# Parking_System.net
KiCad netlist of a schematic drawn in Altium Designer
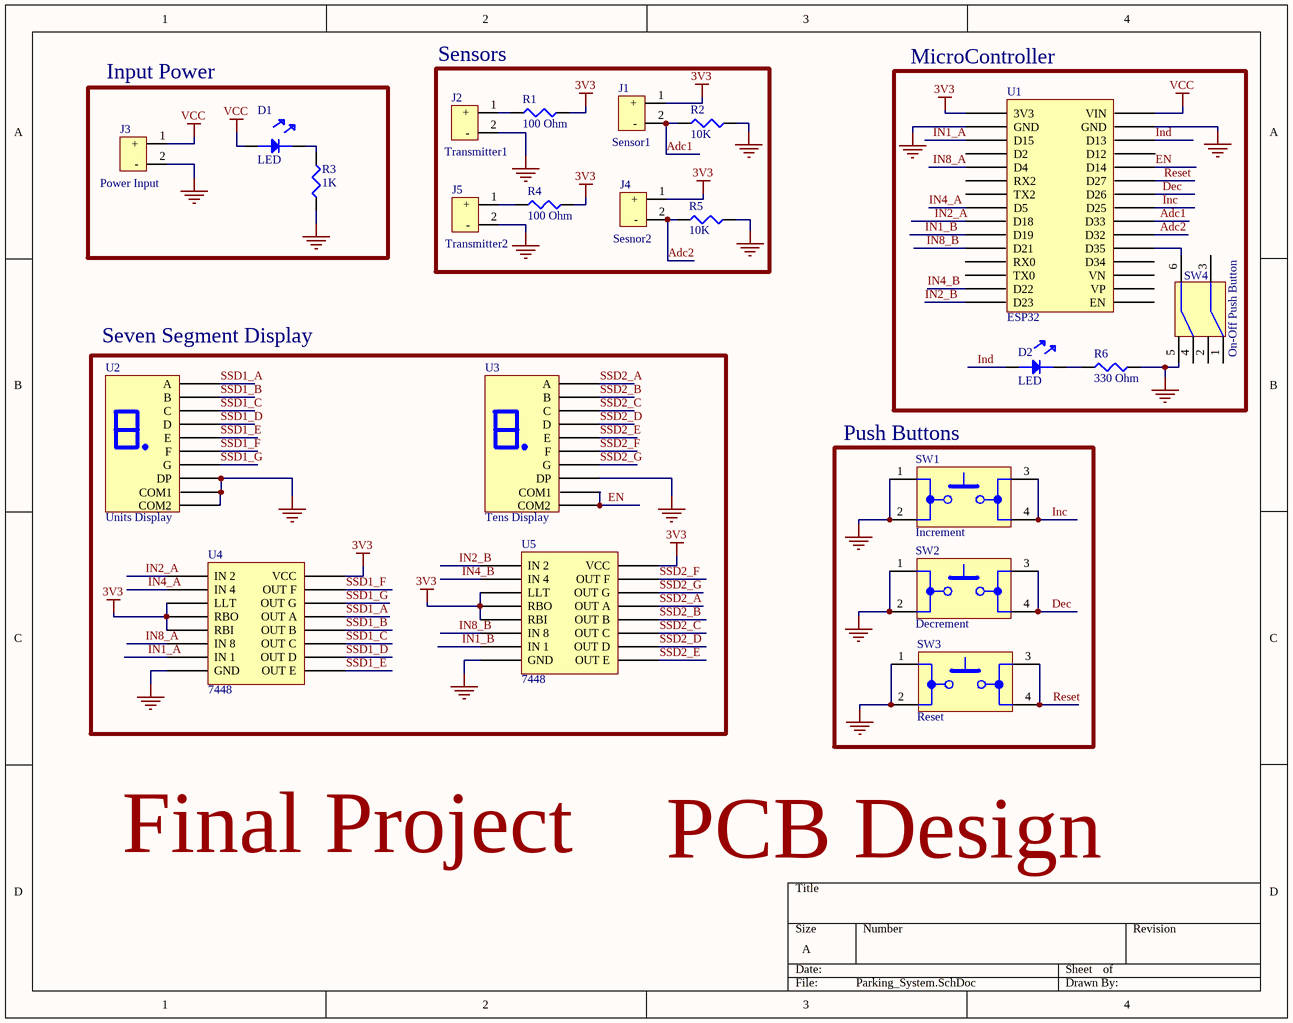
[diagram p0: Parking_System.SchDoc]

(export (version "E")
  (design (tool "Eeschema 10.0.6"))
  (components
    (comp (ref "D1") (value "LED") (footprint "LED-05 R") (libsource (lib "yehia") (part "LED")))
    (comp (ref "D2") (value "LED") (footprint "LED-05 R") (libsource (lib "yehia") (part "LED")))
    (comp (ref "J1")
      (value "Sensor1")
      (footprint "CON")
      (description "Conn Terminal Blocks 2 POS 5mm Solder ST Thru-Hole 16A")
      (fields (field (name "VOLTAGE") "300V"))
      (libsource (lib "yehia") (part "1935161"))
    )
    (comp (ref "J2")
      (value "Transmitter1")
      (footprint "CON")
      (description "Conn Terminal Blocks 2 POS 5mm Solder ST Thru-Hole 16A")
      (fields (field (name "VOLTAGE") "300V"))
      (libsource (lib "yehia") (part "1935161"))
    )
    (comp (ref "J3")
      (value "Power Input")
      (footprint "CON")
      (description "Conn Terminal Blocks 2 POS 5mm Solder ST Thru-Hole 16A")
      (fields (field (name "VOLTAGE") "300V"))
      (libsource (lib "yehia") (part "1935161"))
    )
    (comp (ref "J4")
      (value "Sesnor2")
      (footprint "CON")
      (description "Conn Terminal Blocks 2 POS 5mm Solder ST Thru-Hole 16A")
      (fields (field (name "VOLTAGE") "300V"))
      (libsource (lib "yehia") (part "1935161"))
    )
    (comp (ref "J5")
      (value "Transmitter2")
      (footprint "CON")
      (description "Conn Terminal Blocks 2 POS 5mm Solder ST Thru-Hole 16A")
      (fields (field (name "VOLTAGE") "300V"))
      (libsource (lib "yehia") (part "1935161"))
    )
    (comp (ref "R1") (value "100 Ohm") (footprint "Resistor") (libsource (lib "yehia") (part "Resistor")))
    (comp (ref "R2") (value "10K") (footprint "Resistor") (libsource (lib "yehia") (part "Resistor")))
    (comp (ref "R3") (value "1K") (footprint "Resistor") (libsource (lib "yehia") (part "Resistor")))
    (comp (ref "R4") (value "100 Ohm") (footprint "Resistor") (libsource (lib "yehia") (part "Resistor")))
    (comp (ref "R5") (value "10K") (footprint "Resistor") (libsource (lib "yehia") (part "Resistor")))
    (comp (ref "R6") (value "330 Ohm") (footprint "Resistor") (libsource (lib "yehia") (part "Resistor")))
    (comp (ref "SW1")
      (value "Increment")
      (footprint "DIP4 SW")
      (libsource (lib "yehia") (part "Push Button"))
    )
    (comp (ref "SW2")
      (value "Decrement")
      (footprint "DIP4 SW")
      (libsource (lib "yehia") (part "Push Button"))
    )
    (comp (ref "SW3") (value "Reset") (footprint "DIP4 SW") (libsource (lib "yehia") (part "Push Button")))
    (comp (ref "SW4")
      (value "On-Off Push Button")
      (footprint "DIP6 - SW")
      (libsource (lib "yehia") (part "On-Off Push Button"))
    )
    (comp (ref "U1") (value "ESP32") (footprint "ESP32") (libsource (lib "yehia") (part "ESP32")))
    (comp (ref "U2")
      (value "Units Display")
      (footprint "SSD")
      (description "Seven Segment Display\r\nCoomin Cathode")
      (libsource (lib "yehia") (part "SSD"))
    )
    (comp (ref "U3")
      (value "Tens Display")
      (footprint "SSD")
      (description "Seven Segment Display\r\nCoomin Cathode")
      (libsource (lib "") (part "SSD_1"))
    )
    (comp (ref "U4")
      (value "7448")
      (footprint "DIP16")
      (description "BCD to 7 segment decoder\r\nCommon Cathode")
      (libsource (lib "") (part "7448_1"))
    )
    (comp (ref "U5")
      (value "7448")
      (footprint "DIP16")
      (description "BCD to 7 segment decoder\r\nCommon Cathode")
      (libsource (lib "yehia") (part "7448"))
    )
  )
  (nets
    (net (code "1") (name "/Adc1") (class "Default")
      (node (ref "J1") (pin "2") (pinfunction "-_2") (pintype "passive"))
      (node (ref "R2") (pin "1") (pinfunction "1_1") (pintype "passive"))
      (node (ref "U1") (pin "22") (pinfunction "D33_22") (pintype "passive"))
    )
    (net (code "2") (name "/Adc2") (class "Default")
      (node (ref "J4") (pin "2") (pinfunction "-_2") (pintype "passive"))
      (node (ref "R5") (pin "1") (pinfunction "1_1") (pintype "passive"))
      (node (ref "U1") (pin "21") (pinfunction "D32_21") (pintype "passive"))
    )
    (net (code "3") (name "/Dec") (class "Default")
      (node (ref "SW2") (pin "3") (pinfunction "3_3") (pintype "passive"))
      (node (ref "SW2") (pin "4") (pinfunction "4_4") (pintype "passive"))
      (node (ref "U1") (pin "24") (pinfunction "D26_24") (pintype "passive"))
    )
    (net (code "4") (name "/EN") (class "Default")
      (node (ref "U1") (pin "26") (pinfunction "D14_26") (pintype "passive"))
      (node (ref "U3") (pin "3") (pinfunction "COM1_3") (pintype "passive"))
      (node (ref "U3") (pin "8") (pinfunction "COM2_8") (pintype "passive"))
    )
    (net (code "5") (name "/IN1_A") (class "Default")
      (node (ref "U1") (pin "3") (pinfunction "D15_3") (pintype "passive"))
      (node (ref "U4") (pin "7") (pinfunction "IN_1_7") (pintype "passive"))
    )
    (net (code "6") (name "/IN1_B") (class "Default")
      (node (ref "U1") (pin "10") (pinfunction "D19_10") (pintype "passive"))
      (node (ref "U5") (pin "7") (pinfunction "IN_1_7") (pintype "passive"))
    )
    (net (code "7") (name "/IN2_A") (class "Default")
      (node (ref "U1") (pin "9") (pinfunction "D18_9") (pintype "passive"))
      (node (ref "U4") (pin "1") (pinfunction "IN_2_1") (pintype "passive"))
    )
    (net (code "8") (name "/IN2_B") (class "Default")
      (node (ref "U1") (pin "15") (pinfunction "D23_15") (pintype "passive"))
      (node (ref "U5") (pin "1") (pinfunction "IN_2_1") (pintype "passive"))
    )
    (net (code "9") (name "/IN4_A") (class "Default")
      (node (ref "U1") (pin "8") (pinfunction "D5_8") (pintype "passive"))
      (node (ref "U4") (pin "2") (pinfunction "IN_4_2") (pintype "passive"))
    )
    (net (code "10") (name "/IN4_B") (class "Default")
      (node (ref "U1") (pin "14") (pinfunction "D22_14") (pintype "passive"))
      (node (ref "U5") (pin "2") (pinfunction "IN_4_2") (pintype "passive"))
    )
    (net (code "11") (name "/IN8_A") (class "Default")
      (node (ref "U1") (pin "5") (pinfunction "D4_5") (pintype "passive"))
      (node (ref "U4") (pin "6") (pinfunction "IN_8_6") (pintype "passive"))
    )
    (net (code "12") (name "/IN8_B") (class "Default")
      (node (ref "U1") (pin "11") (pinfunction "D21_11") (pintype "passive"))
      (node (ref "U5") (pin "6") (pinfunction "IN_8_6") (pintype "passive"))
    )
    (net (code "13") (name "/Inc") (class "Default")
      (node (ref "SW1") (pin "3") (pinfunction "3_3") (pintype "passive"))
      (node (ref "SW1") (pin "4") (pinfunction "4_4") (pintype "passive"))
      (node (ref "U1") (pin "23") (pinfunction "D25_23") (pintype "passive"))
    )
    (net (code "14") (name "/Ind") (class "Default")
      (node (ref "D2") (pin "2") (pinfunction "Anode_2") (pintype "passive"))
      (node (ref "U1") (pin "28") (pinfunction "D13_28") (pintype "passive"))
    )
    (net (code "15") (name "/Reset") (class "Default")
      (node (ref "SW3") (pin "3") (pinfunction "3_3") (pintype "passive"))
      (node (ref "SW3") (pin "4") (pinfunction "4_4") (pintype "passive"))
      (node (ref "U1") (pin "25") (pinfunction "D27_25") (pintype "passive"))
    )
    (net (code "16") (name "/SSD1_A") (class "Default")
      (node (ref "U2") (pin "7") (pinfunction "A_7") (pintype "passive"))
      (node (ref "U4") (pin "13") (pinfunction "OUT_A_13") (pintype "passive"))
    )
    (net (code "17") (name "/SSD1_B") (class "Default")
      (node (ref "U2") (pin "6") (pinfunction "B_6") (pintype "passive"))
      (node (ref "U4") (pin "12") (pinfunction "OUT_B_12") (pintype "passive"))
    )
    (net (code "18") (name "/SSD1_C") (class "Default")
      (node (ref "U2") (pin "4") (pinfunction "C_4") (pintype "passive"))
      (node (ref "U4") (pin "11") (pinfunction "OUT_C_11") (pintype "passive"))
    )
    (net (code "19") (name "/SSD1_D") (class "Default")
      (node (ref "U2") (pin "2") (pinfunction "D_2") (pintype "passive"))
      (node (ref "U4") (pin "10") (pinfunction "OUT_D_10") (pintype "passive"))
    )
    (net (code "20") (name "/SSD1_E") (class "Default")
      (node (ref "U2") (pin "1") (pinfunction "E_1") (pintype "passive"))
      (node (ref "U4") (pin "9") (pinfunction "OUT_E_9") (pintype "passive"))
    )
    (net (code "21") (name "/SSD1_F") (class "Default")
      (node (ref "U2") (pin "9") (pinfunction "F_9") (pintype "passive"))
      (node (ref "U4") (pin "15") (pinfunction "OUT_F_15") (pintype "passive"))
    )
    (net (code "22") (name "/SSD1_G") (class "Default")
      (node (ref "U2") (pin "10") (pinfunction "G_10") (pintype "passive"))
      (node (ref "U4") (pin "14") (pinfunction "OUT_G_14") (pintype "passive"))
    )
    (net (code "23") (name "/SSD2_A") (class "Default")
      (node (ref "U3") (pin "7") (pinfunction "A_7") (pintype "passive"))
      (node (ref "U5") (pin "13") (pinfunction "OUT_A_13") (pintype "passive"))
    )
    (net (code "24") (name "/SSD2_B") (class "Default")
      (node (ref "U3") (pin "6") (pinfunction "B_6") (pintype "passive"))
      (node (ref "U5") (pin "12") (pinfunction "OUT_B_12") (pintype "passive"))
    )
    (net (code "25") (name "/SSD2_C") (class "Default")
      (node (ref "U3") (pin "4") (pinfunction "C_4") (pintype "passive"))
      (node (ref "U5") (pin "11") (pinfunction "OUT_C_11") (pintype "passive"))
    )
    (net (code "26") (name "/SSD2_D") (class "Default")
      (node (ref "U3") (pin "2") (pinfunction "D_2") (pintype "passive"))
      (node (ref "U5") (pin "10") (pinfunction "OUT_D_10") (pintype "passive"))
    )
    (net (code "27") (name "/SSD2_E") (class "Default")
      (node (ref "U3") (pin "1") (pinfunction "E_1") (pintype "passive"))
      (node (ref "U5") (pin "9") (pinfunction "OUT_E_9") (pintype "passive"))
    )
    (net (code "28") (name "/SSD2_F") (class "Default")
      (node (ref "U3") (pin "9") (pinfunction "F_9") (pintype "passive"))
      (node (ref "U5") (pin "15") (pinfunction "OUT_F_15") (pintype "passive"))
    )
    (net (code "29") (name "/SSD2_G") (class "Default")
      (node (ref "U3") (pin "10") (pinfunction "G_10") (pintype "passive"))
      (node (ref "U5") (pin "14") (pinfunction "OUT_G_14") (pintype "passive"))
    )
    (net (code "30") (name "3V3") (class "Default")
      (node (ref "J1") (pin "1") (pinfunction "+_1") (pintype "passive"))
      (node (ref "J4") (pin "1") (pinfunction "+_1") (pintype "passive"))
      (node (ref "R1") (pin "2") (pinfunction "2_2") (pintype "passive"))
      (node (ref "R4") (pin "2") (pinfunction "2_2") (pintype "passive"))
      (node (ref "U1") (pin "1") (pinfunction "3V3_1") (pintype "passive"))
      (node (ref "U4") (pin "16") (pinfunction "VCC_16") (pintype "passive"))
      (node (ref "U4") (pin "3") (pinfunction "LLT_3") (pintype "passive"))
      (node (ref "U4") (pin "4") (pinfunction "RBO_4") (pintype "passive"))
      (node (ref "U4") (pin "5") (pinfunction "RBI_5") (pintype "passive"))
      (node (ref "U5") (pin "16") (pinfunction "VCC_16") (pintype "passive"))
      (node (ref "U5") (pin "3") (pinfunction "LLT_3") (pintype "passive"))
      (node (ref "U5") (pin "4") (pinfunction "RBO_4") (pintype "passive"))
      (node (ref "U5") (pin "5") (pinfunction "RBI_5") (pintype "passive"))
    )
    (net (code "31") (name "GND") (class "Default")
      (node (ref "J2") (pin "2") (pinfunction "-_2") (pintype "passive"))
      (node (ref "J3") (pin "2") (pinfunction "-_2") (pintype "passive"))
      (node (ref "J5") (pin "2") (pinfunction "-_2") (pintype "passive"))
      (node (ref "R2") (pin "2") (pinfunction "2_2") (pintype "passive"))
      (node (ref "R3") (pin "1") (pinfunction "1_1") (pintype "passive"))
      (node (ref "R5") (pin "2") (pinfunction "2_2") (pintype "passive"))
      (node (ref "R6") (pin "2") (pinfunction "2_2") (pintype "passive"))
      (node (ref "SW1") (pin "1") (pinfunction "1_1") (pintype "passive"))
      (node (ref "SW1") (pin "2") (pinfunction "2_2") (pintype "passive"))
      (node (ref "SW2") (pin "1") (pinfunction "1_1") (pintype "passive"))
      (node (ref "SW2") (pin "2") (pinfunction "2_2") (pintype "passive"))
      (node (ref "SW3") (pin "1") (pinfunction "1_1") (pintype "passive"))
      (node (ref "SW3") (pin "2") (pinfunction "2_2") (pintype "passive"))
      (node (ref "SW4") (pin "5") (pinfunction "5_5") (pintype "passive"))
      (node (ref "U1") (pin "2") (pinfunction "GND_2") (pintype "passive"))
      (node (ref "U1") (pin "29") (pinfunction "GND_29") (pintype "passive"))
      (node (ref "U2") (pin "3") (pinfunction "COM1_3") (pintype "passive"))
      (node (ref "U2") (pin "5") (pinfunction "DP_5") (pintype "passive"))
      (node (ref "U2") (pin "8") (pinfunction "COM2_8") (pintype "passive"))
      (node (ref "U3") (pin "5") (pinfunction "DP_5") (pintype "passive"))
      (node (ref "U4") (pin "8") (pinfunction "GND_8") (pintype "passive"))
      (node (ref "U5") (pin "8") (pinfunction "GND_8") (pintype "passive"))
    )
    (net (code "32") (name "Net-(D1-Cathode)") (class "Default")
      (node (ref "D1") (pin "1") (pinfunction "Cathode_1") (pintype "passive"))
      (node (ref "R3") (pin "2") (pinfunction "2_2") (pintype "passive"))
    )
    (net (code "33") (name "Net-(D2-Cathode)") (class "Default")
      (node (ref "D2") (pin "1") (pinfunction "Cathode_1") (pintype "passive"))
      (node (ref "R6") (pin "1") (pinfunction "1_1") (pintype "passive"))
    )
    (net (code "34") (name "Net-(J2-+)") (class "Default")
      (node (ref "J2") (pin "1") (pinfunction "+_1") (pintype "passive"))
      (node (ref "R1") (pin "1") (pinfunction "1_1") (pintype "passive"))
    )
    (net (code "35") (name "Net-(J5-+)") (class "Default")
      (node (ref "J5") (pin "1") (pinfunction "+_1") (pintype "passive"))
      (node (ref "R4") (pin "1") (pinfunction "1_1") (pintype "passive"))
    )
    (net (code "36") (name "Net-(U1-D35)") (class "Default")
      (node (ref "SW4") (pin "6") (pinfunction "6_6") (pintype "passive"))
      (node (ref "U1") (pin "20") (pinfunction "D35_20") (pintype "passive"))
    )
    (net (code "37") (name "VCC") (class "Default")
      (node (ref "D1") (pin "2") (pinfunction "Anode_2") (pintype "passive"))
      (node (ref "J3") (pin "1") (pinfunction "+_1") (pintype "passive"))
      (node (ref "U1") (pin "30") (pinfunction "VIN_30") (pintype "passive"))
    )
    (net (code "38") (name "unconnected-(SW4-Pad1)") (class "Default")
      (node (ref "SW4") (pin "1") (pinfunction "1_1") (pintype "passive"))
    )
    (net (code "39") (name "unconnected-(SW4-Pad2)") (class "Default")
      (node (ref "SW4") (pin "2") (pinfunction "2_2") (pintype "passive"))
    )
    (net (code "40") (name "unconnected-(SW4-Pad3)") (class "Default")
      (node (ref "SW4") (pin "3") (pinfunction "3_3") (pintype "passive"))
    )
    (net (code "41") (name "unconnected-(SW4-Pad4)") (class "Default")
      (node (ref "SW4") (pin "4") (pinfunction "4_4") (pintype "passive"))
    )
    (net (code "42") (name "unconnected-(U1-D2-Pad4)") (class "Default")
      (node (ref "U1") (pin "4") (pinfunction "D2_4") (pintype "passive"))
    )
    (net (code "43") (name "unconnected-(U1-D12-Pad27)") (class "Default")
      (node (ref "U1") (pin "27") (pinfunction "D12_27") (pintype "passive"))
    )
    (net (code "44") (name "unconnected-(U1-D34-Pad19)") (class "Default")
      (node (ref "U1") (pin "19") (pinfunction "D34_19") (pintype "passive"))
    )
    (net (code "45") (name "unconnected-(U1-EN-Pad16)") (class "Default")
      (node (ref "U1") (pin "16") (pinfunction "EN_16") (pintype "passive"))
    )
    (net (code "46") (name "unconnected-(U1-RX0-Pad12)") (class "Default")
      (node (ref "U1") (pin "12") (pinfunction "RX0_12") (pintype "passive"))
    )
    (net (code "47") (name "unconnected-(U1-RX2-Pad6)") (class "Default")
      (node (ref "U1") (pin "6") (pinfunction "RX2_6") (pintype "passive"))
    )
    (net (code "48") (name "unconnected-(U1-TX0-Pad13)") (class "Default")
      (node (ref "U1") (pin "13") (pinfunction "TX0_13") (pintype "passive"))
    )
    (net (code "49") (name "unconnected-(U1-TX2-Pad7)") (class "Default")
      (node (ref "U1") (pin "7") (pinfunction "TX2_7") (pintype "passive"))
    )
    (net (code "50") (name "unconnected-(U1-VN-Pad18)") (class "Default")
      (node (ref "U1") (pin "18") (pinfunction "VN_18") (pintype "passive"))
    )
    (net (code "51") (name "unconnected-(U1-VP-Pad17)") (class "Default")
      (node (ref "U1") (pin "17") (pinfunction "VP_17") (pintype "passive"))
    )
  )
)
